# untitled.net
KiCad netlist of a schematic drawn in EAGLE
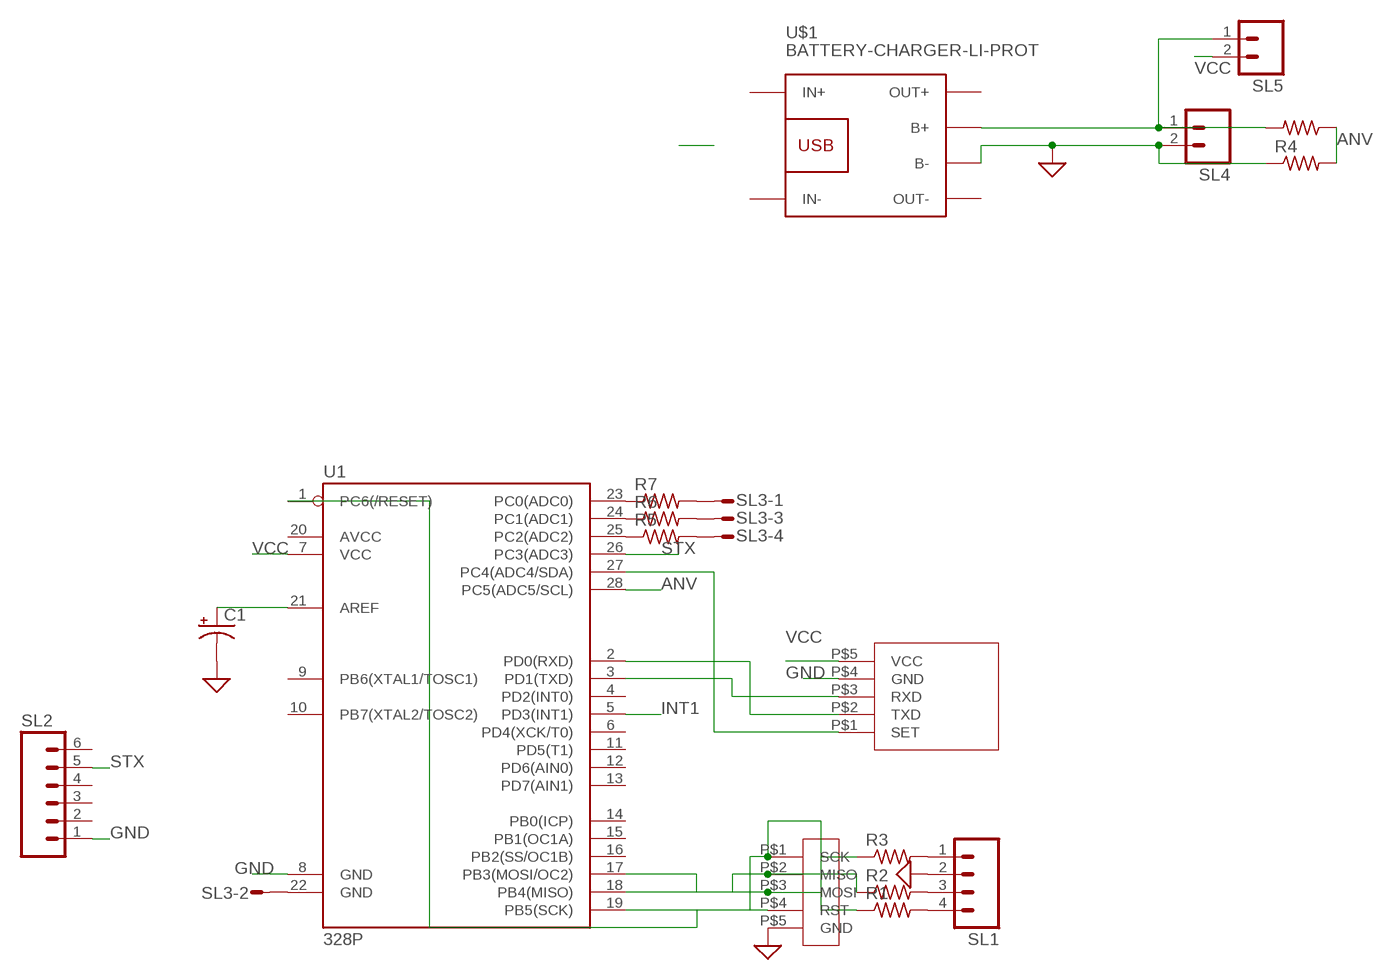
[diagram p0: schematic, sheet 1]

(export (version "E")
  (design (tool "Eeschema 10.0.6"))
  (components
    (comp (ref "C1")
      (value "CAPACITOR-PE2.5-5")
      (footprint "eagle-import:E2,5-5")
      (libsource (lib "eagle-import") (part "CAPACITOR-PE2.5-5"))
    )
    (comp (ref "R1")
      (value "R-US_0204/2V")
      (footprint "eagle-import:0204V")
      (libsource (lib "eagle-import") (part "R-US_0204/2V"))
    )
    (comp (ref "R2")
      (value "R-US_0204/2V")
      (footprint "eagle-import:0204V")
      (libsource (lib "eagle-import") (part "R-US_0204/2V"))
    )
    (comp (ref "R3")
      (value "R-US_0207/7")
      (footprint "eagle-import:0207_7")
      (libsource (lib "eagle-import") (part "R-US_0207/7"))
    )
    (comp (ref "R4")
      (value "R-US_0617/17")
      (footprint "eagle-import:0617_17")
      (libsource (lib "eagle-import") (part "R-US_0617/17"))
    )
    (comp (ref "R5")
      (value "R-US_0204/2V")
      (footprint "eagle-import:0204V")
      (libsource (lib "eagle-import") (part "R-US_0204/2V"))
    )
    (comp (ref "R6")
      (value "R-US_0204/2V")
      (footprint "eagle-import:0204V")
      (libsource (lib "eagle-import") (part "R-US_0204/2V"))
    )
    (comp (ref "R7")
      (value "R-US_0207/5V")
      (footprint "eagle-import:0207_5V")
      (libsource (lib "eagle-import") (part "R-US_0207/5V"))
    )
    (comp (ref "R8")
      (value "R-US_0617/17")
      (footprint "eagle-import:0617_17")
      (libsource (lib "eagle-import") (part "R-US_0617/17"))
    )
    (comp (ref "SL1")
      (value "M04")
      (footprint "eagle-import:04P")
      (libsource (lib "eagle-import") (part "M04"))
    )
    (comp (ref "SL2")
      (value "M06")
      (footprint "eagle-import:06P")
      (libsource (lib "eagle-import") (part "M06"))
    )
    (comp (ref "SL3")
      (value "M04S")
      (footprint "eagle-import:04P")
      (libsource (lib "eagle-import") (part "M04S"))
    )
    (comp (ref "SL4")
      (value "M02")
      (footprint "eagle-import:02P")
      (libsource (lib "eagle-import") (part "M02"))
    )
    (comp (ref "SL5")
      (value "M02")
      (footprint "eagle-import:02P")
      (libsource (lib "eagle-import") (part "M02"))
    )
    (comp (ref "U$1")
      (value "BATTERY-CHARGER-LI-PROT")
      (footprint "eagle-import:BATTERY-CHARGER-LI-PROT")
      (libsource (lib "eagle-import") (part "BATTERY-CHARGER-LI-PROT"))
    )
    (comp (ref "U$2")
      (value "MYISP")
      (footprint "eagle-import:MYISP")
      (libsource (lib "eagle-import") (part "MYISP"))
    )
    (comp (ref "U$3")
      (value "HC12")
      (footprint "eagle-import:HC12")
      (libsource (lib "eagle-import") (part "HC12"))
    )
    (comp (ref "U1")
      (value "328P")
      (footprint "eagle-import:DIP28")
      (libsource (lib "eagle-import") (part "ATMEGA328P_PDIP"))
    )
  )
  (nets
    (net (code "1") (name "/ANV") (class "Default")
      (node (ref "R4") (pin "2") (pinfunction "2_2") (pintype "passive"))
      (node (ref "R8") (pin "1") (pinfunction "1_1") (pintype "passive"))
      (node (ref "U1") (pin "28") (pinfunction "PC5(ADC5/SCL)_28") (pintype "bidirectional"))
    )
    (net (code "2") (name "/INT1") (class "Default")
      (node (ref "U1") (pin "5") (pinfunction "PD3(INT1)_5") (pintype "bidirectional"))
    )
    (net (code "3") (name "/STX") (class "Default")
      (node (ref "SL2") (pin "5") (pinfunction "5_5") (pintype "passive"))
      (node (ref "U1") (pin "26") (pinfunction "PC3(ADC3)_26") (pintype "bidirectional"))
    )
    (net (code "4") (name "/VCC") (class "Default")
      (node (ref "SL5") (pin "2") (pinfunction "2_2") (pintype "passive"))
      (node (ref "U$3") (pin "P$5") (pinfunction "VCC_P$5") (pintype "bidirectional"))
      (node (ref "U1") (pin "7") (pinfunction "VCC_7") (pintype "bidirectional"))
    )
    (net (code "5") (name "Net-(R1-Pad2)") (class "Default")
      (node (ref "R1") (pin "2") (pinfunction "2_2") (pintype "passive"))
      (node (ref "SL1") (pin "4") (pinfunction "4_4") (pintype "passive"))
    )
    (net (code "6") (name "Net-(R2-Pad2)") (class "Default")
      (node (ref "R2") (pin "2") (pinfunction "2_2") (pintype "passive"))
      (node (ref "SL1") (pin "3") (pinfunction "3_3") (pintype "passive"))
    )
    (net (code "7") (name "Net-(R3-Pad2)") (class "Default")
      (node (ref "R3") (pin "2") (pinfunction "2_2") (pintype "passive"))
      (node (ref "SL1") (pin "1") (pinfunction "1_1") (pintype "passive"))
    )
    (net (code "8") (name "Net-(R8-Pad2)") (class "Default")
      (node (ref "R8") (pin "2") (pinfunction "2_2") (pintype "passive"))
      (node (ref "SL4") (pin "1") (pinfunction "1_1") (pintype "passive"))
      (node (ref "SL5") (pin "1") (pinfunction "1_1") (pintype "passive"))
      (node (ref "U$1") (pin "B+") (pinfunction "B+_B+") (pintype "bidirectional"))
    )
    (net (code "9") (name "Net-(SL3A-S)") (class "Default")
      (node (ref "R7") (pin "2") (pinfunction "2_2") (pintype "passive"))
      (node (ref "SL3") (pin "1") (pinfunction "S_1") (pintype "passive"))
    )
    (net (code "10") (name "Net-(SL3B-S)") (class "Default")
      (node (ref "SL3") (pin "2") (pinfunction "S_2") (pintype "passive"))
      (node (ref "U1") (pin "22") (pinfunction "GND_22") (pintype "bidirectional"))
    )
    (net (code "11") (name "Net-(SL3C-S)") (class "Default")
      (node (ref "R6") (pin "2") (pinfunction "2_2") (pintype "passive"))
      (node (ref "SL3") (pin "3") (pinfunction "S_3") (pintype "passive"))
    )
    (net (code "12") (name "Net-(SL3D-S)") (class "Default")
      (node (ref "R5") (pin "2") (pinfunction "2_2") (pintype "passive"))
      (node (ref "SL3") (pin "4") (pinfunction "S_4") (pintype "passive"))
    )
    (net (code "13") (name "Net-(U$2-MISO)") (class "Default")
      (node (ref "R2") (pin "1") (pinfunction "1_1") (pintype "passive"))
      (node (ref "U$2") (pin "P$2") (pinfunction "MISO_P$2") (pintype "bidirectional"))
      (node (ref "U1") (pin "18") (pinfunction "PB4(MISO)_18") (pintype "bidirectional"))
    )
    (net (code "14") (name "Net-(U$2-MOSI)") (class "Default")
      (node (ref "R3") (pin "1") (pinfunction "1_1") (pintype "passive"))
      (node (ref "U$2") (pin "P$3") (pinfunction "MOSI_P$3") (pintype "bidirectional"))
      (node (ref "U1") (pin "17") (pinfunction "PB3(MOSI/OC2)_17") (pintype "bidirectional"))
    )
    (net (code "15") (name "Net-(U$2-RST)") (class "Default")
      (node (ref "U$2") (pin "P$4") (pinfunction "RST_P$4") (pintype "bidirectional"))
      (node (ref "U1") (pin "1") (pinfunction "PC6(/RESET)_1") (pintype "bidirectional"))
    )
    (net (code "16") (name "Net-(U$2-SCK)") (class "Default")
      (node (ref "R1") (pin "1") (pinfunction "1_1") (pintype "passive"))
      (node (ref "U$2") (pin "P$1") (pinfunction "SCK_P$1") (pintype "bidirectional"))
      (node (ref "U1") (pin "19") (pinfunction "PB5(SCK)_19") (pintype "bidirectional"))
    )
    (net (code "17") (name "Net-(U$3-RXD)") (class "Default")
      (node (ref "U$3") (pin "P$3") (pinfunction "RXD_P$3") (pintype "bidirectional"))
      (node (ref "U1") (pin "3") (pinfunction "PD1(TXD)_3") (pintype "bidirectional"))
    )
    (net (code "18") (name "Net-(U$3-SET)") (class "Default")
      (node (ref "U$3") (pin "P$1") (pinfunction "SET_P$1") (pintype "bidirectional"))
      (node (ref "U1") (pin "27") (pinfunction "PC4(ADC4/SDA)_27") (pintype "bidirectional"))
    )
    (net (code "19") (name "Net-(U$3-TXD)") (class "Default")
      (node (ref "U$3") (pin "P$2") (pinfunction "TXD_P$2") (pintype "bidirectional"))
      (node (ref "U1") (pin "2") (pinfunction "PD0(RXD)_2") (pintype "bidirectional"))
    )
    (net (code "20") (name "Net-(U1-AREF)") (class "Default")
      (node (ref "C1") (pin "+") (pinfunction "+_+") (pintype "passive"))
      (node (ref "U1") (pin "21") (pinfunction "AREF_21") (pintype "bidirectional"))
    )
    (net (code "21") (name "Net-(U1-PC0(ADC0))") (class "Default")
      (node (ref "R7") (pin "1") (pinfunction "1_1") (pintype "passive"))
      (node (ref "U1") (pin "23") (pinfunction "PC0(ADC0)_23") (pintype "bidirectional"))
    )
    (net (code "22") (name "Net-(U1-PC1(ADC1))") (class "Default")
      (node (ref "R6") (pin "1") (pinfunction "1_1") (pintype "passive"))
      (node (ref "U1") (pin "24") (pinfunction "PC1(ADC1)_24") (pintype "bidirectional"))
    )
    (net (code "23") (name "Net-(U1-PC2(ADC2))") (class "Default")
      (node (ref "R5") (pin "1") (pinfunction "1_1") (pintype "passive"))
      (node (ref "U1") (pin "25") (pinfunction "PC2(ADC2)_25") (pintype "bidirectional"))
    )
    (net (code "24") (name "SUP") (class "Default")
      (node (ref "C1") (pin "-") (pinfunction "-_-") (pintype "passive"))
      (node (ref "R4") (pin "1") (pinfunction "1_1") (pintype "passive"))
      (node (ref "SL1") (pin "2") (pinfunction "2_2") (pintype "passive"))
      (node (ref "SL2") (pin "1") (pinfunction "1_1") (pintype "passive"))
      (node (ref "SL4") (pin "2") (pinfunction "2_2") (pintype "passive"))
      (node (ref "U$1") (pin "B-") (pinfunction "B-_B-") (pintype "bidirectional"))
      (node (ref "U$2") (pin "P$5") (pinfunction "GND_P$5") (pintype "bidirectional"))
      (node (ref "U$3") (pin "P$4") (pinfunction "GND_P$4") (pintype "bidirectional"))
      (node (ref "U1") (pin "8") (pinfunction "GND_8") (pintype "bidirectional"))
    )
    (net (code "25") (name "unconnected-(SL2-Pad2)") (class "Default")
      (node (ref "SL2") (pin "2") (pinfunction "2_2") (pintype "passive"))
    )
    (net (code "26") (name "unconnected-(SL2-Pad3)") (class "Default")
      (node (ref "SL2") (pin "3") (pinfunction "3_3") (pintype "passive"))
    )
    (net (code "27") (name "unconnected-(SL2-Pad4)") (class "Default")
      (node (ref "SL2") (pin "4") (pinfunction "4_4") (pintype "passive"))
    )
    (net (code "28") (name "unconnected-(SL2-Pad6)") (class "Default")
      (node (ref "SL2") (pin "6") (pinfunction "6_6") (pintype "passive"))
    )
    (net (code "29") (name "unconnected-(U$1-PadIN+)") (class "Default")
      (node (ref "U$1") (pin "IN+") (pinfunction "IN+_IN+") (pintype "bidirectional"))
    )
    (net (code "30") (name "unconnected-(U$1-PadIN-)") (class "Default")
      (node (ref "U$1") (pin "IN-") (pinfunction "IN-_IN-") (pintype "bidirectional"))
    )
    (net (code "31") (name "unconnected-(U$1-PadOUT+)") (class "Default")
      (node (ref "U$1") (pin "OUT+") (pinfunction "OUT+_OUT+") (pintype "bidirectional"))
    )
    (net (code "32") (name "unconnected-(U$1-PadOUT-)") (class "Default")
      (node (ref "U$1") (pin "OUT-") (pinfunction "OUT-_OUT-") (pintype "bidirectional"))
    )
    (net (code "33") (name "unconnected-(U1-AVCC-Pad20)") (class "Default")
      (node (ref "U1") (pin "20") (pinfunction "AVCC_20") (pintype "bidirectional"))
    )
    (net (code "34") (name "unconnected-(U1-PB0(ICP)-Pad14)") (class "Default")
      (node (ref "U1") (pin "14") (pinfunction "PB0(ICP)_14") (pintype "bidirectional"))
    )
    (net (code "35") (name "unconnected-(U1-PB1(OC1A)-Pad15)") (class "Default")
      (node (ref "U1") (pin "15") (pinfunction "PB1(OC1A)_15") (pintype "bidirectional"))
    )
    (net (code "36") (name "unconnected-(U1-PB2(SS{slash}OC1B)-Pad16)") (class "Default")
      (node (ref "U1") (pin "16") (pinfunction "PB2(SS/OC1B)_16") (pintype "bidirectional"))
    )
    (net (code "37") (name "unconnected-(U1-PB6(XTAL1{slash}TOSC1)-Pad9)") (class "Default")
      (node (ref "U1") (pin "9") (pinfunction "PB6(XTAL1/TOSC1)_9") (pintype "bidirectional"))
    )
    (net (code "38") (name "unconnected-(U1-PB7(XTAL2{slash}TOSC2)-Pad10)") (class "Default")
      (node (ref "U1") (pin "10") (pinfunction "PB7(XTAL2/TOSC2)_10") (pintype "bidirectional"))
    )
    (net (code "39") (name "unconnected-(U1-PD2(INT0)-Pad4)") (class "Default")
      (node (ref "U1") (pin "4") (pinfunction "PD2(INT0)_4") (pintype "bidirectional"))
    )
    (net (code "40") (name "unconnected-(U1-PD4(XCK{slash}T0)-Pad6)") (class "Default")
      (node (ref "U1") (pin "6") (pinfunction "PD4(XCK/T0)_6") (pintype "bidirectional"))
    )
    (net (code "41") (name "unconnected-(U1-PD5(T1)-Pad11)") (class "Default")
      (node (ref "U1") (pin "11") (pinfunction "PD5(T1)_11") (pintype "bidirectional"))
    )
    (net (code "42") (name "unconnected-(U1-PD6(AIN0)-Pad12)") (class "Default")
      (node (ref "U1") (pin "12") (pinfunction "PD6(AIN0)_12") (pintype "bidirectional"))
    )
    (net (code "43") (name "unconnected-(U1-PD7(AIN1)-Pad13)") (class "Default")
      (node (ref "U1") (pin "13") (pinfunction "PD7(AIN1)_13") (pintype "bidirectional"))
    )
  )
)
